# Prova.net
KiCad netlist of a schematic drawn in EAGLE
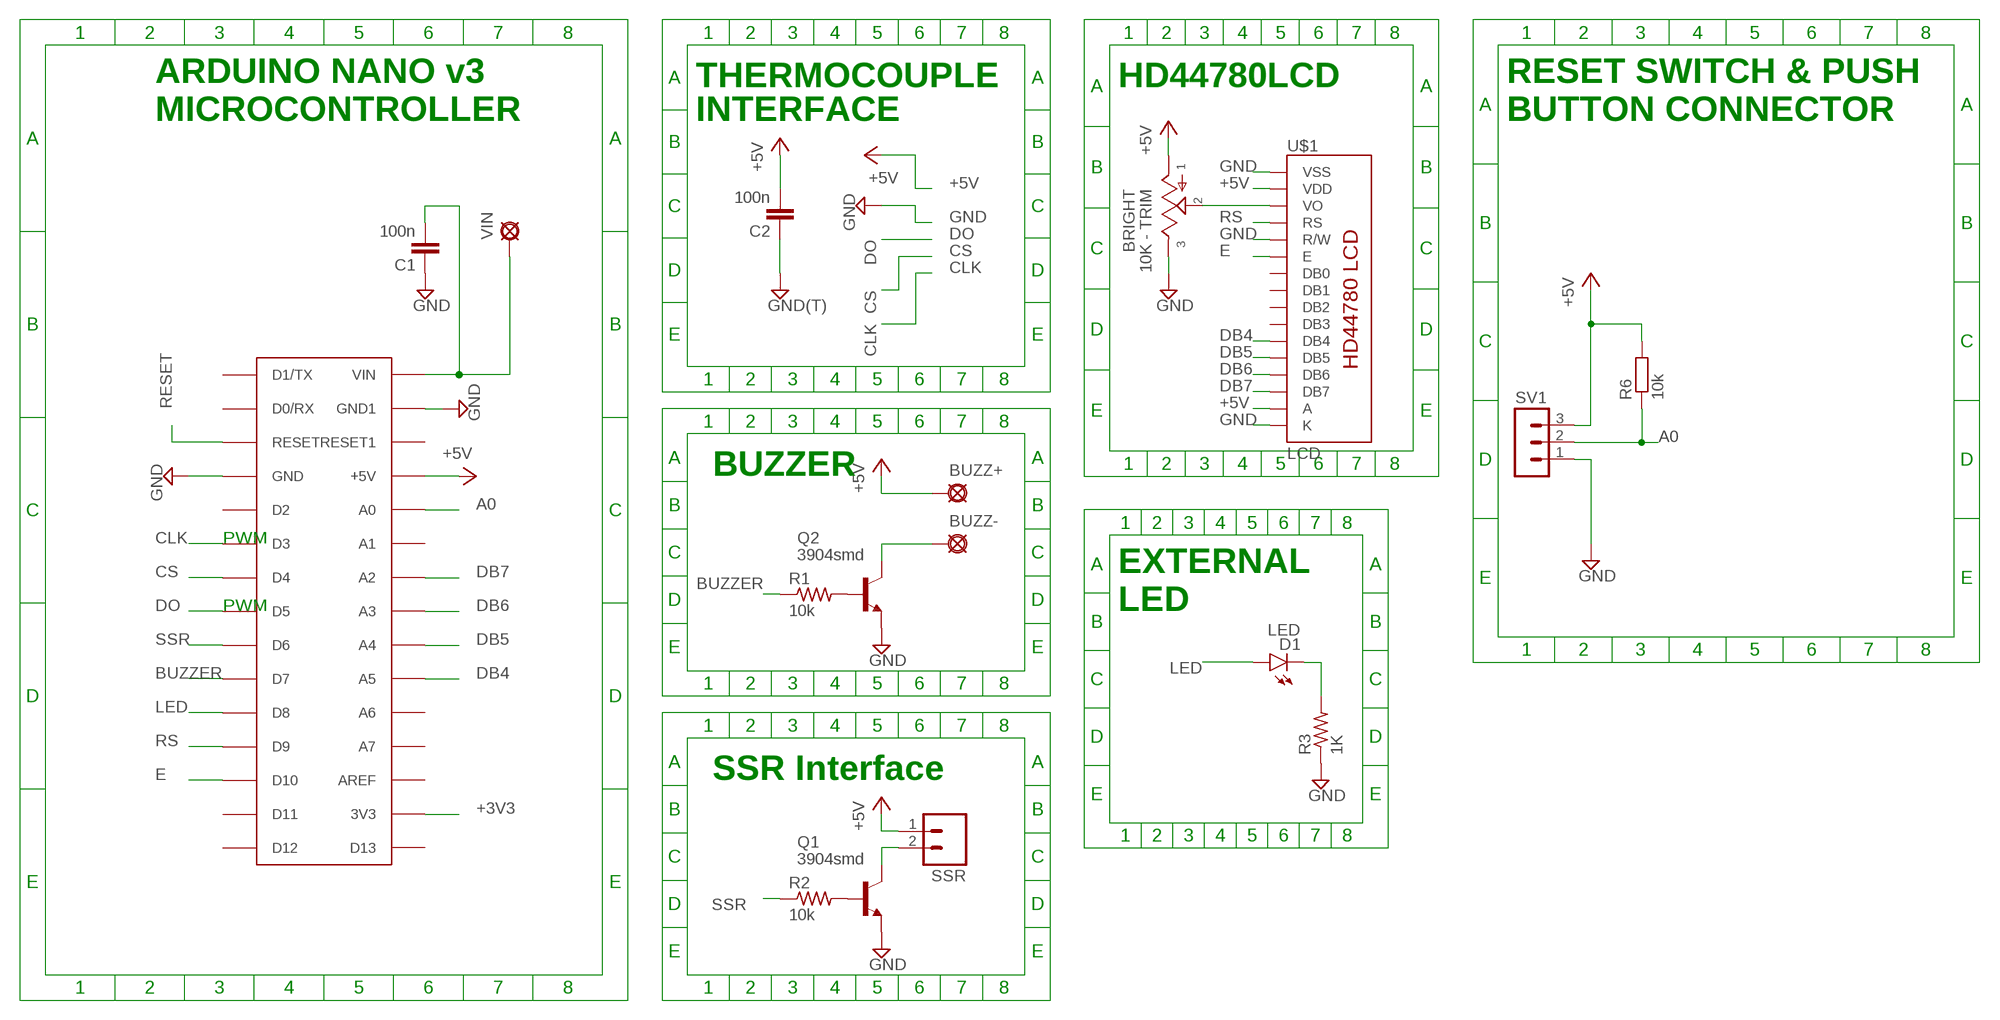
[diagram p0: schematic, sheet 1]
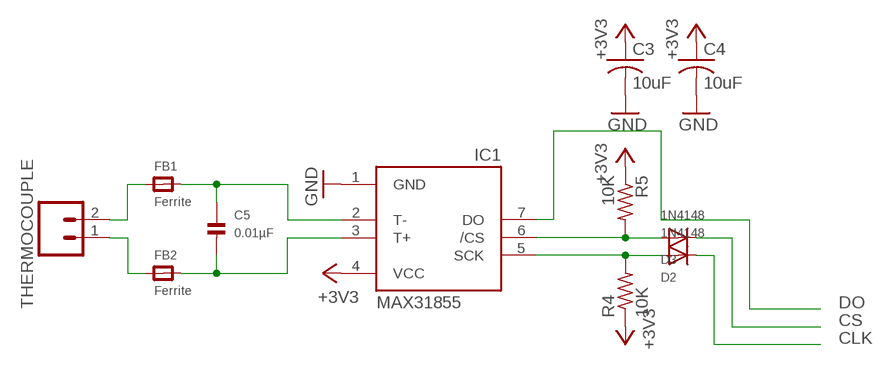
[diagram p1: schematic, sheet 2]

(export (version "E")
  (design (tool "Eeschema 10.0.6"))
  (components
    (comp (ref "C3")
      (value "10uF")
      (footprint "eagle-import:C0805K")
      (libsource (lib "eagle-import") (part "C-USC0805K"))
    )
    (comp (ref "C4")
      (value "10uF")
      (footprint "eagle-import:C0805K")
      (libsource (lib "eagle-import") (part "C-USC0805K"))
    )
    (comp (ref "C5")
      (value "0.01µF")
      (footprint "eagle-import:_0805")
      (libsource (lib "eagle-import") (part "CAP_CERAMIC_0805"))
    )
    (comp (ref "D2")
      (value "1N4148")
      (footprint "eagle-import:DO-1N4148")
      (libsource (lib "eagle-import") (part "DIODEDO-1N4148"))
    )
    (comp (ref "D3")
      (value "1N4148")
      (footprint "eagle-import:DO-1N4148")
      (libsource (lib "eagle-import") (part "DIODEDO-1N4148"))
    )
    (comp (ref "FB1")
      (value "Ferrite")
      (footprint "eagle-import:_0805")
      (libsource (lib "eagle-import") (part "FERRITE_0805"))
    )
    (comp (ref "FB2")
      (value "Ferrite")
      (footprint "eagle-import:_0805")
      (libsource (lib "eagle-import") (part "FERRITE_0805"))
    )
    (comp (ref "IC1")
      (value "MAX31855")
      (footprint "eagle-import:SO08")
      (libsource (lib "eagle-import") (part "MAX6675"))
    )
    (comp (ref "R4")
      (value "10K")
      (footprint "eagle-import:R0805")
      (libsource (lib "eagle-import") (part "R-US_R0805"))
    )
    (comp (ref "R5")
      (value "10K")
      (footprint "eagle-import:R0805")
      (libsource (lib "eagle-import") (part "R-US_R0805"))
    )
    (comp (ref "THERMOCOUPLE")
      (value "M023.5MM")
      (footprint "eagle-import:SCREWTERMINAL-3.5MM-2")
      (libsource (lib "eagle-import") (part "M023.5MM"))
    )
    (comp (ref "ARDUINO")
      (value "Arduino Nano v3.0")
      (footprint "eagle-import:PDIP-32")
      (libsource (lib "eagle-import") (part "ARDUINONANO"))
    )
    (comp (ref "BRIGHT")
      (value "10K - TRIM")
      (footprint "eagle-import:B25P")
      (libsource (lib "eagle-import") (part "POTTRIM"))
    )
    (comp (ref "BUZZ+")
      (value "PAD")
      (footprint "eagle-import:SQUARE")
      (libsource (lib "eagle-import") (part "PAD"))
    )
    (comp (ref "BUZZ-")
      (value "PAD8")
      (footprint "eagle-import:OCTOGON")
      (libsource (lib "eagle-import") (part "PAD8"))
    )
    (comp (ref "C1")
      (value "100n")
      (footprint "eagle-import:0805")
      (libsource (lib "eagle-import") (part "CAP0805"))
    )
    (comp (ref "C2")
      (value "100n")
      (footprint "eagle-import:0805")
      (libsource (lib "eagle-import") (part "CAP0805"))
    )
    (comp (ref "D1")
      (value "LED")
      (footprint "eagle-import:LED3MM")
      (libsource (lib "eagle-import") (part "LED3MM"))
    )
    (comp (ref "GND8")
      (value "GND(T)")
      (footprint "eagle-import:SQUARE")
      (libsource (lib "eagle-import") (part "GND(T)"))
    )
    (comp (ref "Q1")
      (value "3904smd")
      (footprint "eagle-import:SOT23-BEC")
      (libsource (lib "eagle-import") (part "BC850SMD"))
    )
    (comp (ref "Q2")
      (value "3904smd")
      (footprint "eagle-import:SOT23-BEC")
      (libsource (lib "eagle-import") (part "BC850SMD"))
    )
    (comp (ref "R1")
      (value "10k")
      (footprint "eagle-import:R0207_3")
      (libsource (lib "eagle-import") (part "6MM.3"))
    )
    (comp (ref "R2")
      (value "10k")
      (footprint "eagle-import:R0207_3")
      (libsource (lib "eagle-import") (part "6MM.3"))
    )
    (comp (ref "R3")
      (value "1K")
      (footprint "eagle-import:R0207_3")
      (libsource (lib "eagle-import") (part "6MM.3"))
    )
    (comp (ref "R6")
      (value "10k")
      (footprint "eagle-import:M0805")
      (libsource (lib "eagle-import") (part "R-EU_M0805"))
    )
    (comp (ref "SSR")
      (value "M023.5MM")
      (footprint "eagle-import:SCREWTERMINAL-3.5MM-2")
      (libsource (lib "eagle-import") (part "M023.5MM"))
    )
    (comp (ref "SV1")
      (value "MA03-1")
      (footprint "eagle-import:MA03-1")
      (libsource (lib "eagle-import") (part "MA03-1"))
    )
    (comp (ref "U$1")
      (value "LCD")
      (footprint "eagle-import:LCD-16X2-PIN")
      (libsource (lib "eagle-import") (part "LCD-HD44780"))
    )
    (comp (ref "VIN")
      (value "PAD")
      (footprint "eagle-import:SQUARE")
      (libsource (lib "eagle-import") (part "PAD"))
    )
  )
  (nets
    (net (code "1") (name "+3V3") (class "Default")
      (node (ref "ARDUINO") (pin "3V3") (pinfunction "3V3_3V3") (pintype "bidirectional"))
      (node (ref "C3") (pin "1") (pinfunction "1_1") (pintype "passive"))
      (node (ref "C4") (pin "1") (pinfunction "1_1") (pintype "passive"))
      (node (ref "IC1") (pin "4") (pinfunction "VCC_4") (pintype "power_in"))
      (node (ref "R4") (pin "1") (pinfunction "1_1") (pintype "passive"))
      (node (ref "R5") (pin "1") (pinfunction "1_1") (pintype "passive"))
    )
    (net (code "2") (name "+5V") (class "Default")
      (node (ref "ARDUINO") (pin "+5V") (pinfunction "+5V_+5V") (pintype "bidirectional"))
      (node (ref "BRIGHT") (pin "1") (pinfunction "1_1") (pintype "passive"))
      (node (ref "BUZZ+") (pin "1") (pinfunction "PAD_1") (pintype "passive"))
      (node (ref "C2") (pin "2") (pinfunction "2_2") (pintype "passive"))
      (node (ref "R6") (pin "2") (pinfunction "2_2") (pintype "passive"))
      (node (ref "SSR") (pin "1") (pinfunction "1_1") (pintype "passive"))
      (node (ref "SV1") (pin "3") (pinfunction "3_3") (pintype "passive"))
      (node (ref "U$1") (pin "15") (pinfunction "A_15") (pintype "power_in"))
      (node (ref "U$1") (pin "2") (pinfunction "VDD_2") (pintype "power_in"))
    )
    (net (code "3") (name "A0") (class "Default")
      (node (ref "ARDUINO") (pin "A0") (pinfunction "A0_A0") (pintype "bidirectional"))
      (node (ref "R6") (pin "1") (pinfunction "1_1") (pintype "passive"))
      (node (ref "SV1") (pin "2") (pinfunction "2_2") (pintype "passive"))
    )
    (net (code "4") (name "BUZZER") (class "Default")
      (node (ref "ARDUINO") (pin "D7") (pinfunction "D7_D7") (pintype "bidirectional"))
      (node (ref "R1") (pin "1") (pinfunction "1_1") (pintype "passive"))
    )
    (net (code "5") (name "CLK") (class "Default")
      (node (ref "ARDUINO") (pin "D3") (pinfunction "D3_D3") (pintype "bidirectional"))
      (node (ref "D2") (pin "C") (pinfunction "C_C") (pintype "passive"))
    )
    (net (code "6") (name "CS") (class "Default")
      (node (ref "ARDUINO") (pin "D4") (pinfunction "D4_D4") (pintype "bidirectional"))
      (node (ref "D3") (pin "C") (pinfunction "C_C") (pintype "passive"))
    )
    (net (code "7") (name "DB4") (class "Default")
      (node (ref "ARDUINO") (pin "A5") (pinfunction "A5_A5") (pintype "bidirectional"))
      (node (ref "U$1") (pin "11") (pinfunction "DB4_11") (pintype "bidirectional"))
    )
    (net (code "8") (name "DB5") (class "Default")
      (node (ref "ARDUINO") (pin "A4") (pinfunction "A4_A4") (pintype "bidirectional"))
      (node (ref "U$1") (pin "12") (pinfunction "DB5_12") (pintype "bidirectional"))
    )
    (net (code "9") (name "DB6") (class "Default")
      (node (ref "ARDUINO") (pin "A3") (pinfunction "A3_A3") (pintype "bidirectional"))
      (node (ref "U$1") (pin "13") (pinfunction "DB6_13") (pintype "bidirectional"))
    )
    (net (code "10") (name "DB7") (class "Default")
      (node (ref "ARDUINO") (pin "A2") (pinfunction "A2_A2") (pintype "bidirectional"))
      (node (ref "U$1") (pin "14") (pinfunction "DB7_14") (pintype "bidirectional"))
    )
    (net (code "11") (name "DO") (class "Default")
      (node (ref "ARDUINO") (pin "D5") (pinfunction "D5_D5") (pintype "bidirectional"))
      (node (ref "IC1") (pin "7") (pinfunction "DO_7") (pintype "output"))
    )
    (net (code "12") (name "E") (class "Default")
      (node (ref "ARDUINO") (pin "D10") (pinfunction "D10_D10") (pintype "bidirectional"))
      (node (ref "U$1") (pin "6") (pinfunction "E_6") (pintype "input"))
    )
    (net (code "13") (name "GND") (class "Default")
      (node (ref "ARDUINO") (pin "GND") (pinfunction "GND_GND") (pintype "bidirectional"))
      (node (ref "ARDUINO") (pin "GND1") (pinfunction "GND1_GND1") (pintype "bidirectional"))
      (node (ref "BRIGHT") (pin "3") (pinfunction "3_3") (pintype "passive"))
      (node (ref "C1") (pin "1") (pinfunction "1_1") (pintype "passive"))
      (node (ref "C2") (pin "1") (pinfunction "1_1") (pintype "passive"))
      (node (ref "C3") (pin "2") (pinfunction "2_2") (pintype "passive"))
      (node (ref "C4") (pin "2") (pinfunction "2_2") (pintype "passive"))
      (node (ref "GND8") (pin "1") (pinfunction "GND_1") (pintype "power_in"))
      (node (ref "IC1") (pin "1") (pinfunction "GND_1") (pintype "power_in"))
      (node (ref "Q1") (pin "E") (pinfunction "E_E") (pintype "passive"))
      (node (ref "Q2") (pin "E") (pinfunction "E_E") (pintype "passive"))
      (node (ref "R3") (pin "1") (pinfunction "1_1") (pintype "passive"))
      (node (ref "SV1") (pin "1") (pinfunction "1_1") (pintype "passive"))
      (node (ref "U$1") (pin "1") (pinfunction "VSS_1") (pintype "power_in"))
      (node (ref "U$1") (pin "16") (pinfunction "K_16") (pintype "power_in"))
      (node (ref "U$1") (pin "5") (pinfunction "R/W_5") (pintype "input"))
    )
    (net (code "14") (name "LED") (class "Default")
      (node (ref "ARDUINO") (pin "D8") (pinfunction "D8_D8") (pintype "bidirectional"))
      (node (ref "D1") (pin "A") (pinfunction "A_A") (pintype "passive"))
    )
    (net (code "15") (name "Net-(BUZZ--PAD)") (class "Default")
      (node (ref "BUZZ-") (pin "1") (pinfunction "PAD_1") (pintype "passive"))
      (node (ref "Q2") (pin "C") (pinfunction "C_C") (pintype "passive"))
    )
    (net (code "16") (name "Net-(C5-P$1)") (class "Default")
      (node (ref "C5") (pin "1") (pinfunction "P$1_1") (pintype "passive"))
      (node (ref "FB1") (pin "2") (pinfunction "P$2_2") (pintype "passive"))
      (node (ref "IC1") (pin "2") (pinfunction "T-_2") (pintype "input"))
    )
    (net (code "17") (name "Net-(C5-P$2)") (class "Default")
      (node (ref "C5") (pin "2") (pinfunction "P$2_2") (pintype "passive"))
      (node (ref "FB2") (pin "2") (pinfunction "P$2_2") (pintype "passive"))
      (node (ref "IC1") (pin "3") (pinfunction "T+_3") (pintype "input"))
    )
    (net (code "18") (name "Net-(D1-C)") (class "Default")
      (node (ref "D1") (pin "K") (pinfunction "C_K") (pintype "passive"))
      (node (ref "R3") (pin "2") (pinfunction "2_2") (pintype "passive"))
    )
    (net (code "19") (name "Net-(FB1-P$1)") (class "Default")
      (node (ref "FB1") (pin "1") (pinfunction "P$1_1") (pintype "passive"))
      (node (ref "THERMOCOUPLE") (pin "2") (pinfunction "2_2") (pintype "passive"))
    )
    (net (code "20") (name "Net-(FB2-P$1)") (class "Default")
      (node (ref "FB2") (pin "1") (pinfunction "P$1_1") (pintype "passive"))
      (node (ref "THERMOCOUPLE") (pin "1") (pinfunction "1_1") (pintype "passive"))
    )
    (net (code "21") (name "Net-(IC1-SCK)") (class "Default")
      (node (ref "D2") (pin "A") (pinfunction "A_A") (pintype "passive"))
      (node (ref "IC1") (pin "5") (pinfunction "SCK_5") (pintype "input"))
      (node (ref "R4") (pin "2") (pinfunction "2_2") (pintype "passive"))
    )
    (net (code "22") (name "Net-(IC1-{slash}CS)") (class "Default")
      (node (ref "D3") (pin "A") (pinfunction "A_A") (pintype "passive"))
      (node (ref "IC1") (pin "6") (pinfunction "/CS_6") (pintype "input"))
      (node (ref "R5") (pin "2") (pinfunction "2_2") (pintype "passive"))
    )
    (net (code "23") (name "Net-(Q1-PadB)") (class "Default")
      (node (ref "Q1") (pin "B") (pinfunction "B_B") (pintype "passive"))
      (node (ref "R2") (pin "2") (pinfunction "2_2") (pintype "passive"))
    )
    (net (code "24") (name "Net-(Q1-PadC)") (class "Default")
      (node (ref "Q1") (pin "C") (pinfunction "C_C") (pintype "passive"))
      (node (ref "SSR") (pin "2") (pinfunction "2_2") (pintype "passive"))
    )
    (net (code "25") (name "Net-(Q2-PadB)") (class "Default")
      (node (ref "Q2") (pin "B") (pinfunction "B_B") (pintype "passive"))
      (node (ref "R1") (pin "2") (pinfunction "2_2") (pintype "passive"))
    )
    (net (code "26") (name "Net-(U$1-VO)") (class "Default")
      (node (ref "BRIGHT") (pin "2") (pinfunction "2_2") (pintype "passive"))
      (node (ref "U$1") (pin "3") (pinfunction "VO_3") (pintype "bidirectional"))
    )
    (net (code "27") (name "Net-(VIN-PAD)") (class "Default")
      (node (ref "ARDUINO") (pin "VIN") (pinfunction "VIN_VIN") (pintype "bidirectional"))
      (node (ref "C1") (pin "2") (pinfunction "2_2") (pintype "passive"))
      (node (ref "VIN") (pin "1") (pinfunction "PAD_1") (pintype "passive"))
    )
    (net (code "28") (name "RESET") (class "Default")
      (node (ref "ARDUINO") (pin "RESET") (pinfunction "RESET_RESET") (pintype "bidirectional"))
    )
    (net (code "29") (name "RS") (class "Default")
      (node (ref "ARDUINO") (pin "D9") (pinfunction "D9_D9") (pintype "bidirectional"))
      (node (ref "U$1") (pin "4") (pinfunction "RS_4") (pintype "input"))
    )
    (net (code "30") (name "SSR") (class "Default")
      (node (ref "ARDUINO") (pin "D6") (pinfunction "D6_D6") (pintype "bidirectional"))
      (node (ref "R2") (pin "1") (pinfunction "1_1") (pintype "passive"))
    )
    (net (code "31") (name "unconnected-(ARDUINO-PadA1)") (class "Default")
      (node (ref "ARDUINO") (pin "A1") (pinfunction "A1_A1") (pintype "bidirectional"))
    )
    (net (code "32") (name "unconnected-(ARDUINO-PadA6)") (class "Default")
      (node (ref "ARDUINO") (pin "A6") (pinfunction "A6_A6") (pintype "bidirectional"))
    )
    (net (code "33") (name "unconnected-(ARDUINO-PadA7)") (class "Default")
      (node (ref "ARDUINO") (pin "A7") (pinfunction "A7_A7") (pintype "bidirectional"))
    )
    (net (code "34") (name "unconnected-(ARDUINO-PadAREF)") (class "Default")
      (node (ref "ARDUINO") (pin "AREF") (pinfunction "AREF_AREF") (pintype "bidirectional"))
    )
    (net (code "35") (name "unconnected-(ARDUINO-PadD0{slash}RX)") (class "Default")
      (node (ref "ARDUINO") (pin "D0/RX") (pinfunction "D0/RX_D0/RX") (pintype "bidirectional"))
    )
    (net (code "36") (name "unconnected-(ARDUINO-PadD1{slash}TX)") (class "Default")
      (node (ref "ARDUINO") (pin "D1/TX") (pinfunction "D1/TX_D1/TX") (pintype "bidirectional"))
    )
    (net (code "37") (name "unconnected-(ARDUINO-PadD2)") (class "Default")
      (node (ref "ARDUINO") (pin "D2") (pinfunction "D2_D2") (pintype "bidirectional"))
    )
    (net (code "38") (name "unconnected-(ARDUINO-PadD11)") (class "Default")
      (node (ref "ARDUINO") (pin "D11") (pinfunction "D11_D11") (pintype "bidirectional"))
    )
    (net (code "39") (name "unconnected-(ARDUINO-PadD12)") (class "Default")
      (node (ref "ARDUINO") (pin "D12") (pinfunction "D12_D12") (pintype "bidirectional"))
    )
    (net (code "40") (name "unconnected-(ARDUINO-PadD13)") (class "Default")
      (node (ref "ARDUINO") (pin "D13") (pinfunction "D13_D13") (pintype "bidirectional"))
    )
    (net (code "41") (name "unconnected-(ARDUINO-PadRESET1)") (class "Default")
      (node (ref "ARDUINO") (pin "RESET1") (pinfunction "RESET1_RESET1") (pintype "bidirectional"))
    )
    (net (code "42") (name "unconnected-(U$1-DB0-Pad7)") (class "Default")
      (node (ref "U$1") (pin "7") (pinfunction "DB0_7") (pintype "bidirectional"))
    )
    (net (code "43") (name "unconnected-(U$1-DB1-Pad8)") (class "Default")
      (node (ref "U$1") (pin "8") (pinfunction "DB1_8") (pintype "bidirectional"))
    )
    (net (code "44") (name "unconnected-(U$1-DB2-Pad9)") (class "Default")
      (node (ref "U$1") (pin "9") (pinfunction "DB2_9") (pintype "bidirectional"))
    )
    (net (code "45") (name "unconnected-(U$1-DB3-Pad10)") (class "Default")
      (node (ref "U$1") (pin "10") (pinfunction "DB3_10") (pintype "bidirectional"))
    )
  )
)
